# OutPut_LED.net
KiCad netlist of a schematic drawn in Altium Designer
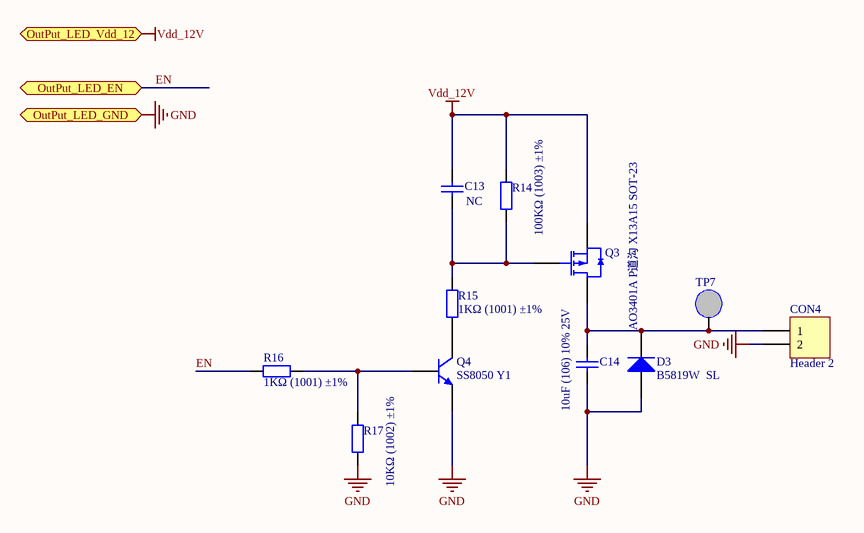
[diagram p0: OutPut_LED.SchDoc]

(export (version "E")
  (design (tool "Eeschema 10.0.6"))
  (components
    (comp (ref "C13")
      (value "NC")
      (footprint "0805_C")
      (description "贴片电容")
      (libsource (lib "Miscellaneous Devices LC") (part "0805 22uF (226) 20% 25V"))
    )
    (comp (ref "C14")
      (value "10uF (106) 10% 25V")
      (footprint "0805_C")
      (description "贴片电容")
      (libsource (lib "Miscellaneous Devices LC") (part "0805 10uF (106) 10% 25V"))
    )
    (comp (ref "CON4")
      (value "Header 2")
      (footprint "PH2.0-WS-2P")
      (description "Header, 2-Pin")
      (fields (field (name "PUBLISHER") "Altium Limited"))
      (libsource (lib "Miscellaneous Connectors") (part "Header 2"))
    )
    (comp (ref "D3")
      (value "B5819W  SL")
      (footprint "SOD-123")
      (description "肖特基二极管")
      (libsource (lib "Miscellaneous Devices LC") (part "SOD-123 B5819W  SL"))
    )
    (comp (ref "Q3")
      (value "AO3401A P道沟 X13A15 SOT-23")
      (footprint "SOT-23-3L")
      (description "MOS(场效应管)")
      (libsource (lib "Miscellaneous Devices LC") (part "AO3401A P道沟 X13A15 SOT-23"))
    )
    (comp (ref "Q4")
      (value "SS8050 Y1")
      (footprint "SOT-23(SOT-23-3)")
      (description "三极管")
      (libsource (lib "Miscellaneous Devices LC") (part "SOT-23 SS8050 Y1"))
    )
    (comp (ref "R14")
      (value "100KΩ (1003) ±1%")
      (footprint "0805_R")
      (description "贴片电阻")
      (libsource (lib "Miscellaneous Devices LC") (part "0805 100KΩ (1003) 1%"))
    )
    (comp (ref "R15")
      (value "1KΩ (1001) ±1%")
      (footprint "0805_R")
      (description "贴片电阻")
      (libsource (lib "") (part "0805 1KΩ (1001) 1%_1"))
    )
    (comp (ref "R16")
      (value "1KΩ (1001) ±1%")
      (footprint "0805_R")
      (description "贴片电阻")
      (libsource (lib "Miscellaneous Devices LC") (part "0805 1KΩ (1001) 1%"))
    )
    (comp (ref "R17")
      (value "10KΩ (1002) ±1%")
      (footprint "0805_R")
      (description "贴片电阻")
      (libsource (lib "Miscellaneous Devices LC") (part "0805 10KΩ (1002) 1%"))
    )
    (comp (ref "TP7") (value "TP") (footprint "TP") (libsource (lib "mylib") (part "TP")))
  )
  (nets
    (net (code "1") (name "/EN") (class "Default")
      (node (ref "R16") (pin "1") (pinfunction "1_1") (pintype "passive"))
    )
    (net (code "2") (name "GND") (class "Default")
      (node (ref "C14") (pin "1") (pinfunction "1_1") (pintype "passive"))
      (node (ref "CON4") (pin "2") (pinfunction "2_2") (pintype "passive"))
      (node (ref "D3") (pin "1") (pinfunction "A_1") (pintype "passive"))
      (node (ref "Q4") (pin "2") (pinfunction "E_2") (pintype "passive"))
      (node (ref "R17") (pin "1") (pinfunction "1_1") (pintype "passive"))
    )
    (net (code "3") (name "Net-(D3-K)") (class "Default")
      (node (ref "C14") (pin "2") (pinfunction "2_2") (pintype "passive"))
      (node (ref "CON4") (pin "1") (pinfunction "1_1") (pintype "passive"))
      (node (ref "D3") (pin "2") (pinfunction "K_2") (pintype "passive"))
      (node (ref "Q3") (pin "3") (pinfunction "D_3") (pintype "passive"))
      (node (ref "TP7") (pin "1") (pinfunction "1_1") (pintype "passive"))
    )
    (net (code "4") (name "Net-(Q3-G)") (class "Default")
      (node (ref "C13") (pin "1") (pinfunction "1_1") (pintype "passive"))
      (node (ref "Q3") (pin "1") (pinfunction "G_1") (pintype "passive"))
      (node (ref "R14") (pin "1") (pinfunction "1_1") (pintype "passive"))
      (node (ref "R15") (pin "1") (pinfunction "1_1") (pintype "passive"))
    )
    (net (code "5") (name "Net-(Q4-B)") (class "Default")
      (node (ref "Q4") (pin "1") (pinfunction "B_1") (pintype "passive"))
      (node (ref "R16") (pin "2") (pinfunction "2_2") (pintype "passive"))
      (node (ref "R17") (pin "2") (pinfunction "2_2") (pintype "passive"))
    )
    (net (code "6") (name "Net-(Q4-C)") (class "Default")
      (node (ref "Q4") (pin "3") (pinfunction "C_3") (pintype "passive"))
      (node (ref "R15") (pin "2") (pinfunction "2_2") (pintype "passive"))
    )
    (net (code "7") (name "Vdd_12V") (class "Default")
      (node (ref "C13") (pin "2") (pinfunction "2_2") (pintype "passive"))
      (node (ref "Q3") (pin "2") (pinfunction "S_2") (pintype "passive"))
      (node (ref "R14") (pin "2") (pinfunction "2_2") (pintype "passive"))
    )
  )
)
